# Sheet1.net
KiCad netlist of a schematic drawn in Altium Designer
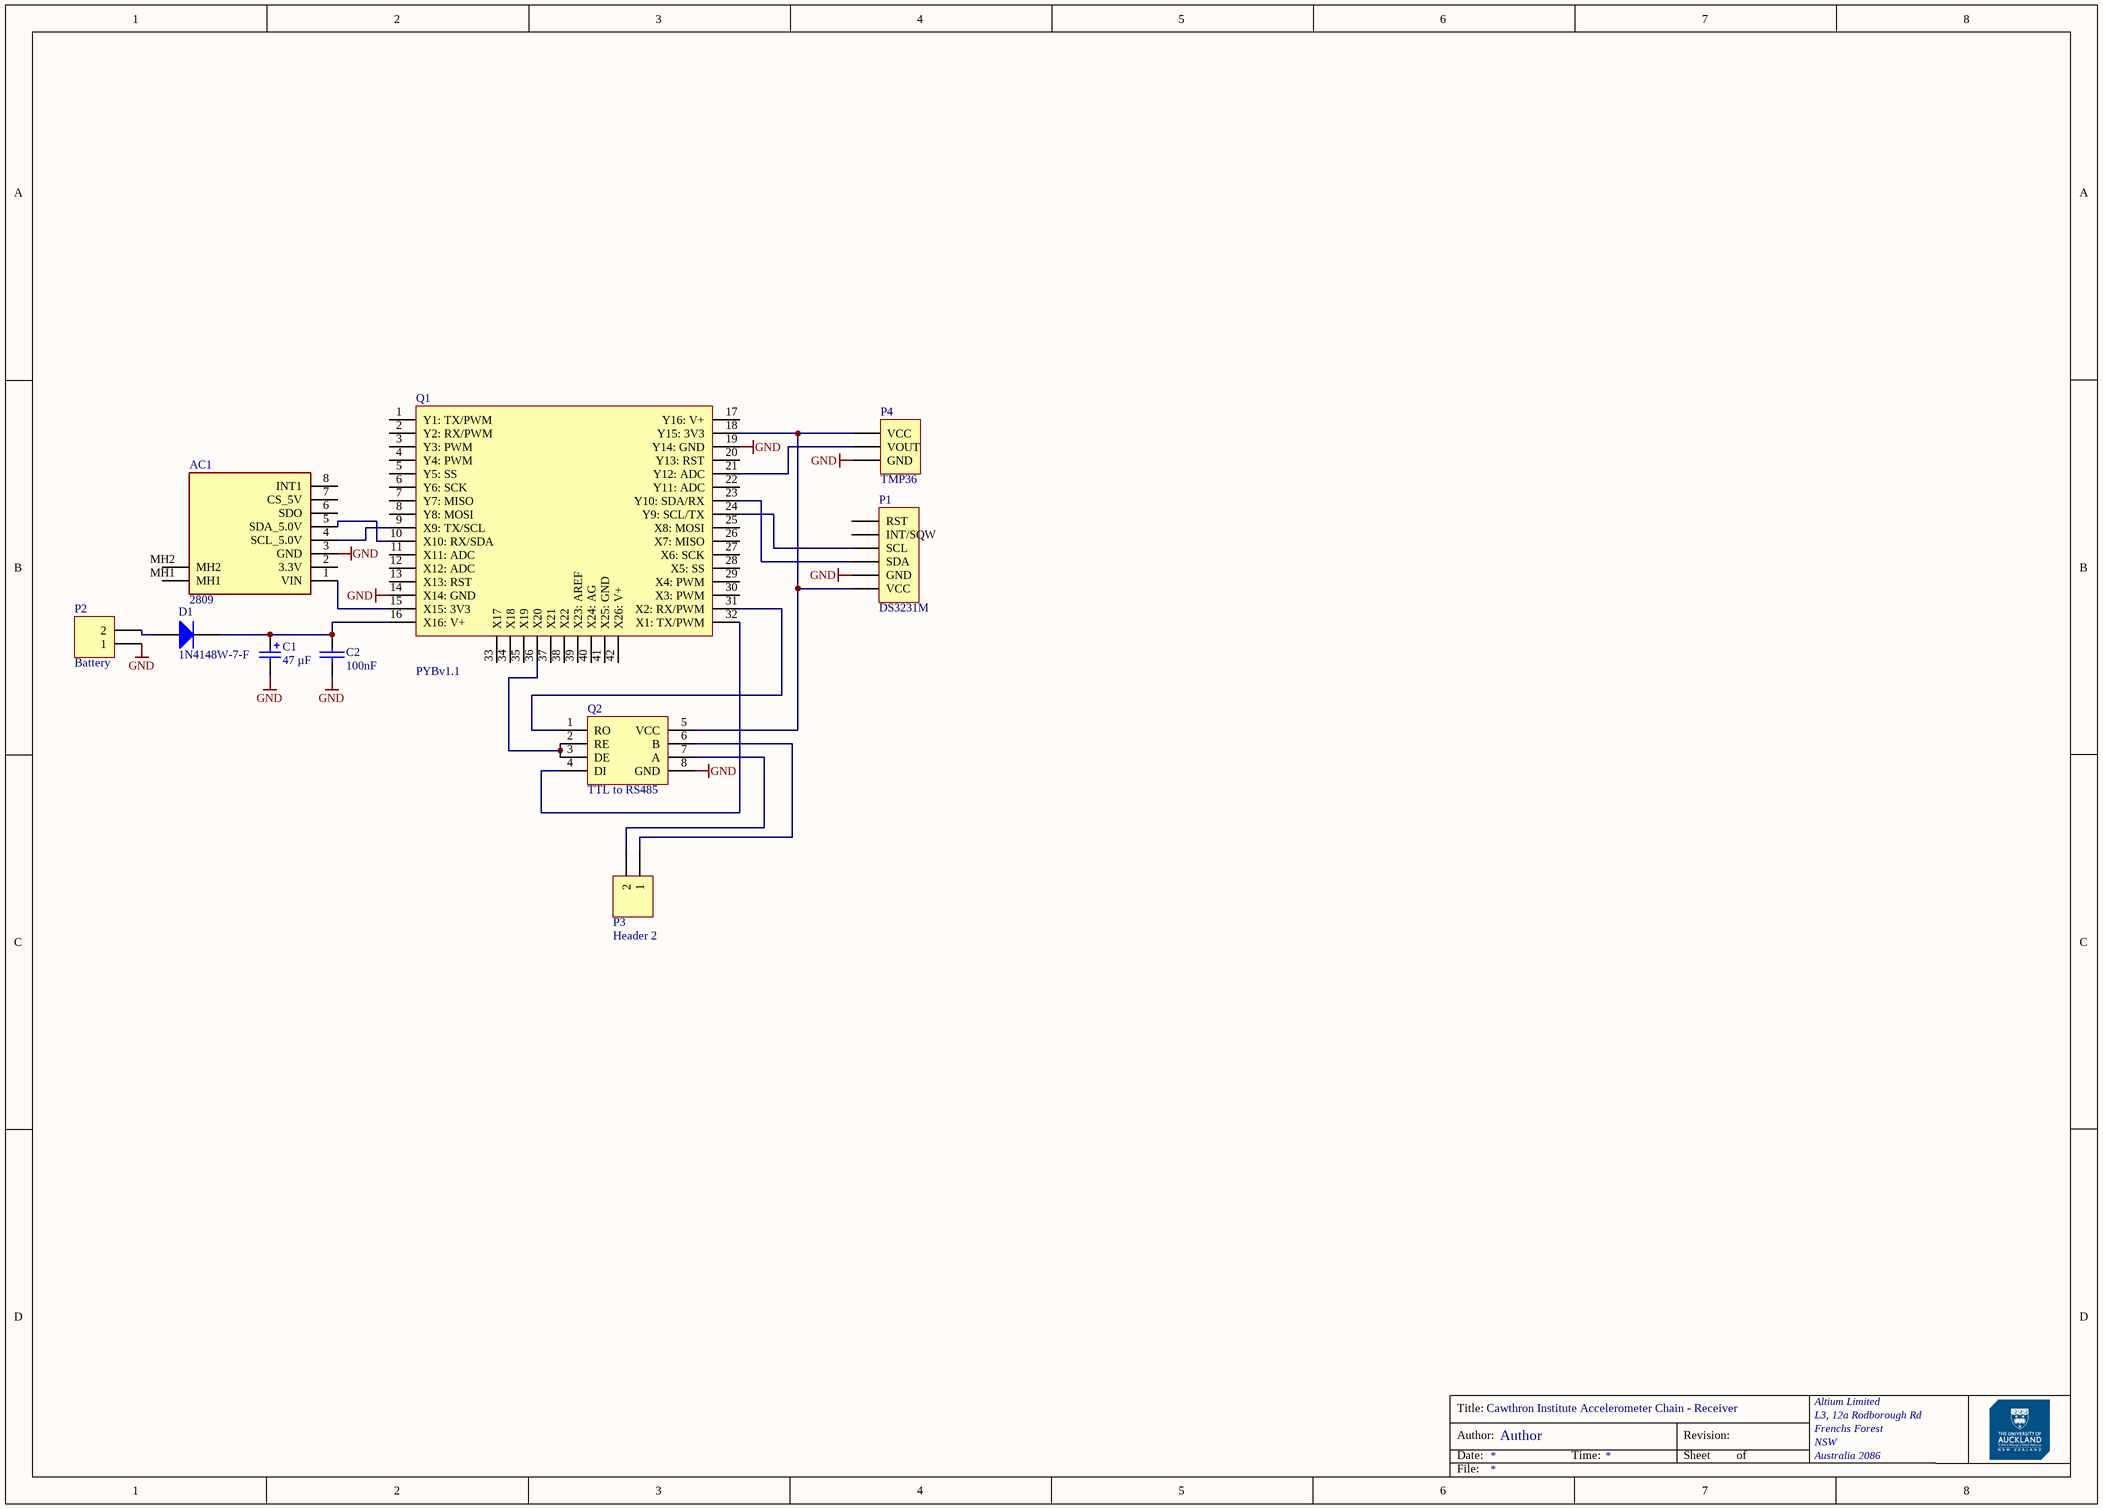
[diagram p0: Sheet1.SchDoc]

(export (version "E")
  (design (tool "Eeschema 10.0.6"))
  (components
    (comp (ref "AC1")
      (value "2809")
      (footprint "SamacSys:2809")
      (description "Accelerometer")
      (fields (field (name "MOUSER PART NUMBER") "485-2809"))
      (libsource (lib "SamacSys") (part "2809"))
    )
    (comp (ref "C1")
      (value "CAP ALUM 22UF 20% 50V SMD")
      (footprint "CAP POL 8x5.4mm SMT")
      (fields
        (field (name "MANUFACTURER") "Nichicon")
        (field (name "MANUFACTURER PART NUMBER") "UWX1V220MCL1GB")
        (field (name "TOLERANCE") "±20%")
        (field (name "CAPACITANCE 1") "47 µF")
      )
      (libsource (lib "EE209V3") (part "SMT-CAP 22uF/35V SM"))
    )
    (comp (ref "C2")
      (value "100nF")
      (footprint "0805 CAP")
      (description "SMT Capacitor Non Polarised")
      (libsource (lib "EE209V3") (part "SMT- Cap"))
    )
    (comp (ref "D1")
      (value "1N4148W-7-F")
      (footprint "SOD123")
      (description "DIODE GEN PURP 100V 300MA SOD123")
      (fields
        (field (name "MANUFACTURER") "Diodes Incorporated")
        (field (name "MANUFACTURER PART NUMBER") "1N4148W-13-F")
      )
      (libsource (lib "EE209V3") (part "SMT-Diode 1N4148W-7-F"))
    )
    (comp (ref "P1")
      (value "DS3231M")
      (footprint "HDR1X6")
      (description "Header, 6-Pin")
      (fields (field (name "PUBLISHER") "Altium Limited"))
      (libsource (lib "Miscellaneous Connectors") (part "Header 6"))
    )
    (comp (ref "P2")
      (value "Battery")
      (footprint "HDR1X2")
      (description "Header, 2-Pin")
      (fields (field (name "PUBLISHER") "Altium Limited"))
      (libsource (lib "") (part "Header 2_1"))
    )
    (comp (ref "P3")
      (value "Header 2")
      (footprint "HDR1X2")
      (description "Header, 2-Pin")
      (fields (field (name "PUBLISHER") "Altium Limited"))
      (libsource (lib "Miscellaneous Connectors") (part "Header 2"))
    )
    (comp (ref "P4")
      (value "TMP36")
      (footprint "HDR1X3")
      (description "Header, 3-Pin")
      (fields (field (name "PUBLISHER") "Altium Limited"))
      (libsource (lib "Miscellaneous Connectors") (part "Header 3"))
    )
    (comp (ref "Q1")
      (value "PYBv1.1")
      (footprint "PcbLib1:PCBComponent_1")
      (description "Microcontroller")
      (libsource (lib "PYBv1.1") (part "PYBv1.1"))
    )
    (comp (ref "Q2")
      (value "TTL to RS485")
      (footprint "PCBComponent_1")
      (description "Converter")
      (libsource (lib "TTL to RS485") (part "TTL to RS485"))
    )
  )
  (nets
    (net (code "1") (name "GND") (class "Default")
      (node (ref "AC1") (pin "3") (pinfunction "GND_3") (pintype "passive"))
      (node (ref "C1") (pin "2") (pinfunction "2_2") (pintype "passive"))
      (node (ref "C2") (pin "2") (pinfunction "2_2") (pintype "passive"))
      (node (ref "P1") (pin "5") (pinfunction "GND_5") (pintype "passive"))
      (node (ref "P2") (pin "1") (pinfunction "1_1") (pintype "passive"))
      (node (ref "P4") (pin "3") (pinfunction "GND_3") (pintype "passive"))
      (node (ref "Q1") (pin "14") (pinfunction "X14:_GND_14") (pintype "passive"))
      (node (ref "Q1") (pin "19") (pinfunction "Y14:_GND_19") (pintype "passive"))
      (node (ref "Q2") (pin "8") (pinfunction "GND_8") (pintype "passive"))
    )
    (net (code "2") (name "Net-(AC1-SCL_5.0V)") (class "Default")
      (node (ref "AC1") (pin "4") (pinfunction "SCL_5.0V_4") (pintype "passive"))
      (node (ref "Q1") (pin "9") (pinfunction "X9:_TX/SCL_9") (pintype "passive"))
    )
    (net (code "3") (name "Net-(AC1-SDA_5.0V)") (class "Default")
      (node (ref "AC1") (pin "5") (pinfunction "SDA_5.0V_5") (pintype "passive"))
      (node (ref "Q1") (pin "10") (pinfunction "X10:_RX/SDA_10") (pintype "passive"))
    )
    (net (code "4") (name "Net-(AC1-VIN)") (class "Default")
      (node (ref "AC1") (pin "1") (pinfunction "VIN_1") (pintype "passive"))
      (node (ref "Q1") (pin "15") (pinfunction "X15:_3V3_15") (pintype "passive"))
    )
    (net (code "5") (name "Net-(D1-A)") (class "Default")
      (node (ref "D1") (pin "1") (pinfunction "A_1") (pintype "passive"))
      (node (ref "P2") (pin "2") (pinfunction "2_2") (pintype "passive"))
    )
    (net (code "6") (name "Net-(D1-K)") (class "Default")
      (node (ref "C1") (pin "1") (pinfunction "1_1") (pintype "passive"))
      (node (ref "C2") (pin "1") (pinfunction "1_1") (pintype "passive"))
      (node (ref "D1") (pin "2") (pinfunction "K_2") (pintype "passive"))
      (node (ref "Q1") (pin "16") (pinfunction "X16:_V+_16") (pintype "passive"))
    )
    (net (code "7") (name "Net-(P1-SCL)") (class "Default")
      (node (ref "P1") (pin "3") (pinfunction "SCL_3") (pintype "passive"))
      (node (ref "Q1") (pin "24") (pinfunction "Y9:_SCL/TX_24") (pintype "passive"))
    )
    (net (code "8") (name "Net-(P1-SDA)") (class "Default")
      (node (ref "P1") (pin "4") (pinfunction "SDA_4") (pintype "passive"))
      (node (ref "Q1") (pin "23") (pinfunction "Y10:_SDA/RX_23") (pintype "passive"))
    )
    (net (code "9") (name "Net-(P1-VCC)") (class "Default")
      (node (ref "P1") (pin "6") (pinfunction "VCC_6") (pintype "passive"))
      (node (ref "P4") (pin "1") (pinfunction "VCC_1") (pintype "passive"))
      (node (ref "Q1") (pin "18") (pinfunction "Y15:_3V3_18") (pintype "passive"))
      (node (ref "Q2") (pin "5") (pinfunction "VCC_5") (pintype "passive"))
    )
    (net (code "10") (name "Net-(P4-VOUT)") (class "Default")
      (node (ref "P4") (pin "2") (pinfunction "VOUT_2") (pintype "passive"))
      (node (ref "Q1") (pin "21") (pinfunction "Y12:_ADC_21") (pintype "passive"))
    )
    (net (code "11") (name "Net-(Q1-X1:_TX{slash}PWM)") (class "Default")
      (node (ref "Q1") (pin "32") (pinfunction "X1:_TX/PWM_32") (pintype "passive"))
      (node (ref "Q2") (pin "4") (pinfunction "DI_4") (pintype "passive"))
    )
    (net (code "12") (name "Net-(Q1-X2:_RX{slash}PWM)") (class "Default")
      (node (ref "Q1") (pin "31") (pinfunction "X2:_RX/PWM_31") (pintype "passive"))
      (node (ref "Q2") (pin "1") (pinfunction "RO_1") (pintype "passive"))
    )
    (net (code "13") (name "Net-(Q1-X20)") (class "Default")
      (node (ref "Q1") (pin "36") (pinfunction "X20_36") (pintype "passive"))
      (node (ref "Q2") (pin "2") (pinfunction "RE_2") (pintype "passive"))
      (node (ref "Q2") (pin "3") (pinfunction "DE_3") (pintype "passive"))
    )
    (net (code "14") (name "Net-(Q2-A)") (class "Default")
      (node (ref "P3") (pin "2") (pinfunction "2_2") (pintype "passive"))
      (node (ref "Q2") (pin "7") (pinfunction "A_7") (pintype "passive"))
    )
    (net (code "15") (name "Net-(Q2-B)") (class "Default")
      (node (ref "P3") (pin "1") (pinfunction "1_1") (pintype "passive"))
      (node (ref "Q2") (pin "6") (pinfunction "B_6") (pintype "passive"))
    )
    (net (code "16") (name "unconnected-(AC1-3.3V-Pad2)") (class "Default")
      (node (ref "AC1") (pin "2") (pinfunction "3.3V_2") (pintype "passive"))
    )
    (net (code "17") (name "unconnected-(AC1-CS_5V-Pad7)") (class "Default")
      (node (ref "AC1") (pin "7") (pinfunction "CS_5V_7") (pintype "passive"))
    )
    (net (code "18") (name "unconnected-(AC1-INT1-Pad8)") (class "Default")
      (node (ref "AC1") (pin "8") (pinfunction "INT1_8") (pintype "passive"))
    )
    (net (code "19") (name "unconnected-(AC1-PadMH1)") (class "Default")
      (node (ref "AC1") (pin "MH1") (pinfunction "MH1_MH1") (pintype "passive"))
    )
    (net (code "20") (name "unconnected-(AC1-PadMH2)") (class "Default")
      (node (ref "AC1") (pin "MH2") (pinfunction "MH2_MH2") (pintype "passive"))
    )
    (net (code "21") (name "unconnected-(AC1-SDO-Pad6)") (class "Default")
      (node (ref "AC1") (pin "6") (pinfunction "SDO_6") (pintype "passive"))
    )
    (net (code "22") (name "unconnected-(P1-INT{slash}SQW-Pad2)") (class "Default")
      (node (ref "P1") (pin "2") (pinfunction "INT/SQW_2") (pintype "passive"))
    )
    (net (code "23") (name "unconnected-(P1-RST-Pad1)") (class "Default")
      (node (ref "P1") (pin "1") (pinfunction "RST_1") (pintype "passive"))
    )
    (net (code "24") (name "unconnected-(Q1-X3:_PWM-Pad30)") (class "Default")
      (node (ref "Q1") (pin "30") (pinfunction "X3:_PWM_30") (pintype "passive"))
    )
    (net (code "25") (name "unconnected-(Q1-X4:_PWM-Pad29)") (class "Default")
      (node (ref "Q1") (pin "29") (pinfunction "X4:_PWM_29") (pintype "passive"))
    )
    (net (code "26") (name "unconnected-(Q1-X5:_SS-Pad28)") (class "Default")
      (node (ref "Q1") (pin "28") (pinfunction "X5:_SS_28") (pintype "passive"))
    )
    (net (code "27") (name "unconnected-(Q1-X6:_SCK-Pad27)") (class "Default")
      (node (ref "Q1") (pin "27") (pinfunction "X6:_SCK_27") (pintype "passive"))
    )
    (net (code "28") (name "unconnected-(Q1-X7:_MISO-Pad26)") (class "Default")
      (node (ref "Q1") (pin "26") (pinfunction "X7:_MISO_26") (pintype "passive"))
    )
    (net (code "29") (name "unconnected-(Q1-X8:_MOSI-Pad25)") (class "Default")
      (node (ref "Q1") (pin "25") (pinfunction "X8:_MOSI_25") (pintype "passive"))
    )
    (net (code "30") (name "unconnected-(Q1-X11:_ADC-Pad11)") (class "Default")
      (node (ref "Q1") (pin "11") (pinfunction "X11:_ADC_11") (pintype "passive"))
    )
    (net (code "31") (name "unconnected-(Q1-X12:_ADC-Pad12)") (class "Default")
      (node (ref "Q1") (pin "12") (pinfunction "X12:_ADC_12") (pintype "passive"))
    )
    (net (code "32") (name "unconnected-(Q1-X13:_RST-Pad13)") (class "Default")
      (node (ref "Q1") (pin "13") (pinfunction "X13:_RST_13") (pintype "passive"))
    )
    (net (code "33") (name "unconnected-(Q1-X17-Pad33)") (class "Default")
      (node (ref "Q1") (pin "33") (pinfunction "X17_33") (pintype "passive"))
    )
    (net (code "34") (name "unconnected-(Q1-X18-Pad34)") (class "Default")
      (node (ref "Q1") (pin "34") (pinfunction "X18_34") (pintype "passive"))
    )
    (net (code "35") (name "unconnected-(Q1-X19-Pad35)") (class "Default")
      (node (ref "Q1") (pin "35") (pinfunction "X19_35") (pintype "passive"))
    )
    (net (code "36") (name "unconnected-(Q1-X21-Pad37)") (class "Default")
      (node (ref "Q1") (pin "37") (pinfunction "X21_37") (pintype "passive"))
    )
    (net (code "37") (name "unconnected-(Q1-X22-Pad38)") (class "Default")
      (node (ref "Q1") (pin "38") (pinfunction "X22_38") (pintype "passive"))
    )
    (net (code "38") (name "unconnected-(Q1-X23:_AREF-Pad39)") (class "Default")
      (node (ref "Q1") (pin "39") (pinfunction "X23:_AREF_39") (pintype "passive"))
    )
    (net (code "39") (name "unconnected-(Q1-X24:_AG-Pad40)") (class "Default")
      (node (ref "Q1") (pin "40") (pinfunction "X24:_AG_40") (pintype "passive"))
    )
    (net (code "40") (name "unconnected-(Q1-X25:_GND-Pad41)") (class "Default")
      (node (ref "Q1") (pin "41") (pinfunction "X25:_GND_41") (pintype "passive"))
    )
    (net (code "41") (name "unconnected-(Q1-X26:_V+-Pad42)") (class "Default")
      (node (ref "Q1") (pin "42") (pinfunction "X26:_V+_42") (pintype "passive"))
    )
    (net (code "42") (name "unconnected-(Q1-Y1:_TX{slash}PWM-Pad1)") (class "Default")
      (node (ref "Q1") (pin "1") (pinfunction "Y1:_TX/PWM_1") (pintype "passive"))
    )
    (net (code "43") (name "unconnected-(Q1-Y2:_RX{slash}PWM-Pad2)") (class "Default")
      (node (ref "Q1") (pin "2") (pinfunction "Y2:_RX/PWM_2") (pintype "passive"))
    )
    (net (code "44") (name "unconnected-(Q1-Y3:_PWM-Pad3)") (class "Default")
      (node (ref "Q1") (pin "3") (pinfunction "Y3:_PWM_3") (pintype "passive"))
    )
    (net (code "45") (name "unconnected-(Q1-Y4:_PWM-Pad4)") (class "Default")
      (node (ref "Q1") (pin "4") (pinfunction "Y4:_PWM_4") (pintype "passive"))
    )
    (net (code "46") (name "unconnected-(Q1-Y5:_SS-Pad5)") (class "Default")
      (node (ref "Q1") (pin "5") (pinfunction "Y5:_SS_5") (pintype "passive"))
    )
    (net (code "47") (name "unconnected-(Q1-Y6:_SCK-Pad6)") (class "Default")
      (node (ref "Q1") (pin "6") (pinfunction "Y6:_SCK_6") (pintype "passive"))
    )
    (net (code "48") (name "unconnected-(Q1-Y7:_MISO-Pad7)") (class "Default")
      (node (ref "Q1") (pin "7") (pinfunction "Y7:_MISO_7") (pintype "passive"))
    )
    (net (code "49") (name "unconnected-(Q1-Y8:_MOSI-Pad8)") (class "Default")
      (node (ref "Q1") (pin "8") (pinfunction "Y8:_MOSI_8") (pintype "passive"))
    )
    (net (code "50") (name "unconnected-(Q1-Y11:_ADC-Pad22)") (class "Default")
      (node (ref "Q1") (pin "22") (pinfunction "Y11:_ADC_22") (pintype "passive"))
    )
    (net (code "51") (name "unconnected-(Q1-Y13:_RST-Pad20)") (class "Default")
      (node (ref "Q1") (pin "20") (pinfunction "Y13:_RST_20") (pintype "passive"))
    )
    (net (code "52") (name "unconnected-(Q1-Y16:_V+-Pad17)") (class "Default")
      (node (ref "Q1") (pin "17") (pinfunction "Y16:_V+_17") (pintype "passive"))
    )
  )
)
